# noisemaker_5-0.net
KiCad netlist of a schematic drawn in EAGLE
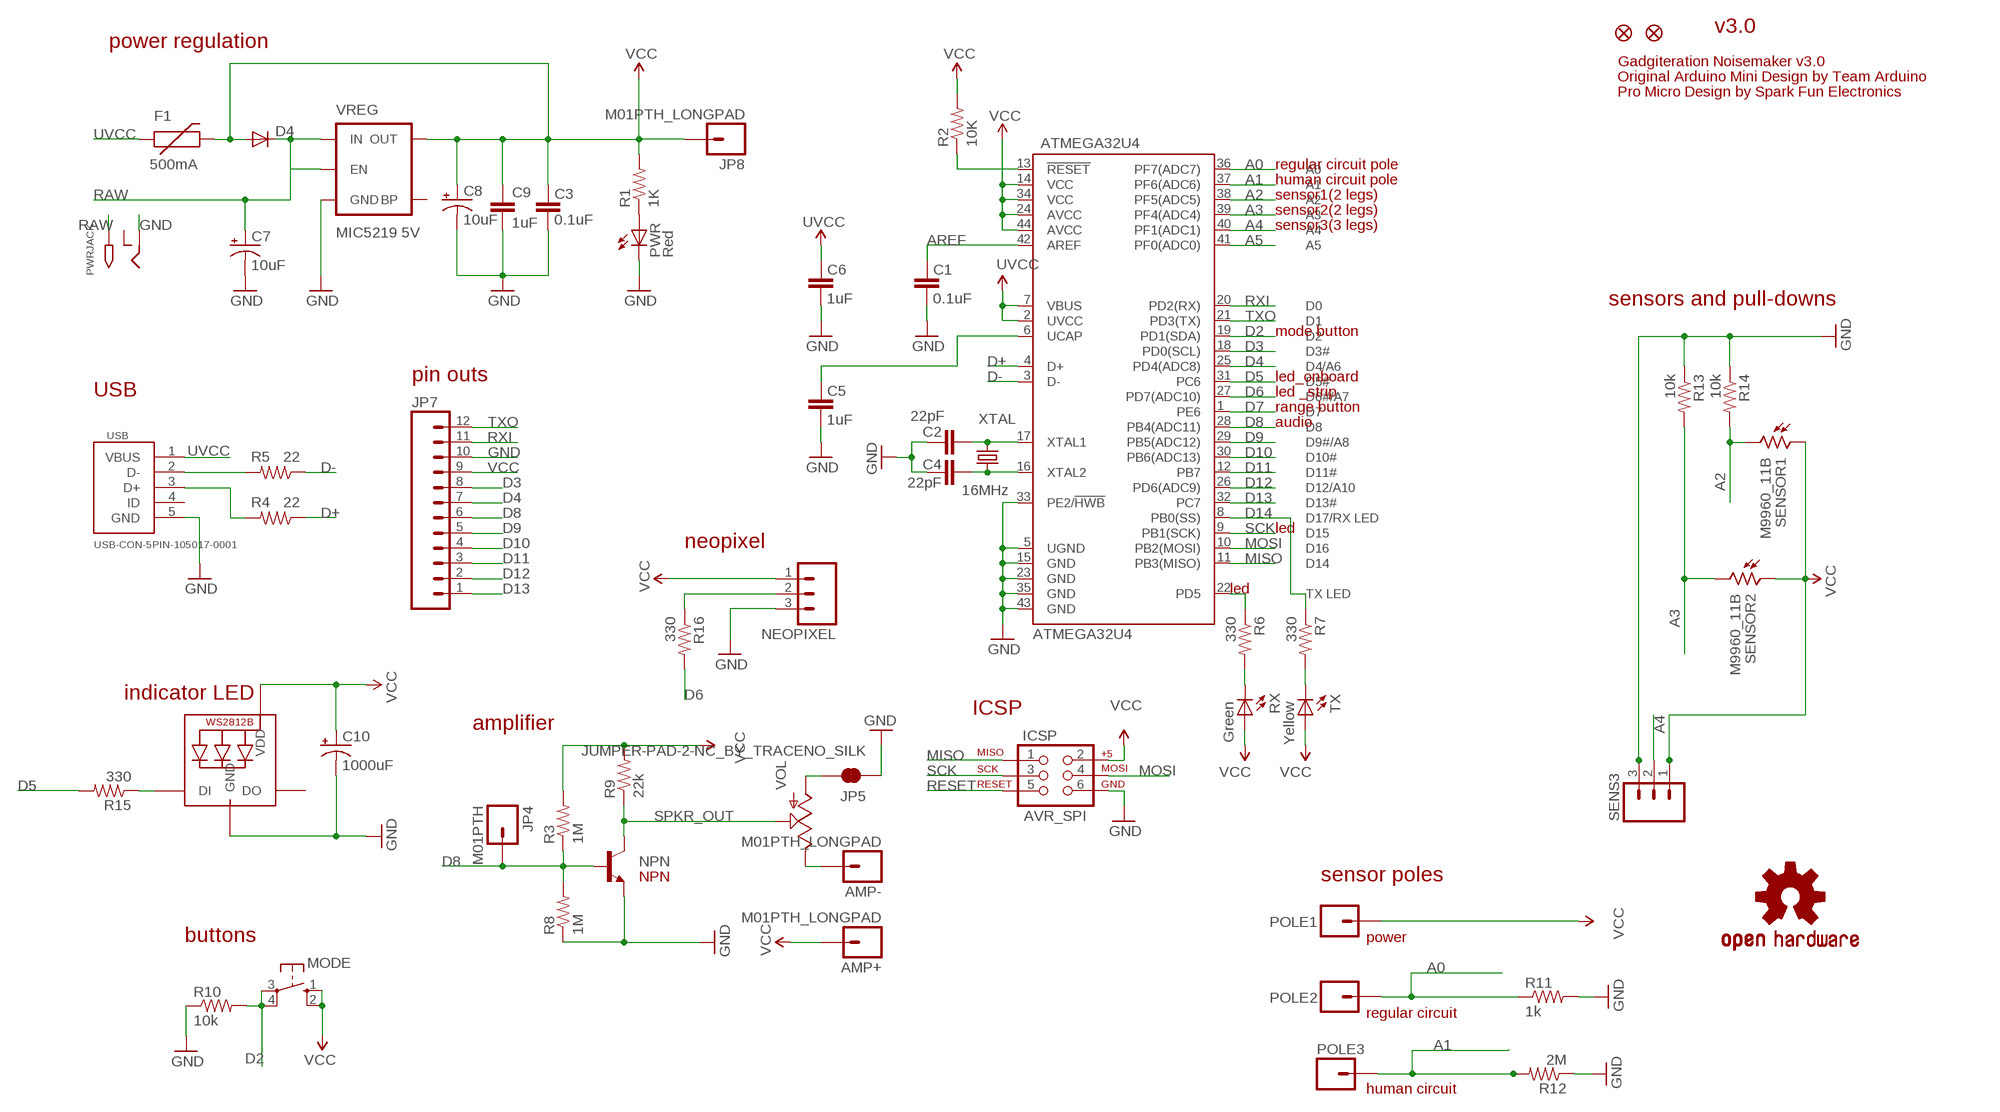
[diagram p0: schematic, sheet 1]

(export (version "E")
  (design (tool "Eeschema 10.0.6"))
  (components
    (comp (ref "AMP+")
      (value "M01PTH_LONGPAD")
      (footprint "eagle-import:1X01_LONGPAD")
      (libsource (lib "eagle-import") (part "M01PTH_LONGPAD"))
    )
    (comp (ref "AMP-")
      (value "M01PTH_LONGPAD")
      (footprint "eagle-import:1X01_LONGPAD")
      (libsource (lib "eagle-import") (part "M01PTH_LONGPAD"))
    )
    (comp (ref "ATMEGA32U4")
      (value "ATMEGA32U4")
      (footprint "eagle-import:SPARKFUN-DIGITALIC_TQFP44")
      (libsource (lib "eagle-import") (part "ATMEGA32U4TQFP"))
    )
    (comp (ref "C1")
      (value "0.1uF")
      (footprint "eagle-import:1206")
      (libsource (lib "eagle-import") (part "SparkFun-Capacitors_CAP1206"))
    )
    (comp (ref "C2")
      (value "22pF")
      (footprint "eagle-import:0603-CAP")
      (libsource (lib "eagle-import") (part "CAP0603-CAP"))
    )
    (comp (ref "C3")
      (value "0.1uF")
      (footprint "eagle-import:1206")
      (libsource (lib "eagle-import") (part "SparkFun-Capacitors_CAP1206"))
    )
    (comp (ref "C4")
      (value "22pF")
      (footprint "eagle-import:0603-CAP")
      (libsource (lib "eagle-import") (part "CAP0603-CAP"))
    )
    (comp (ref "C5")
      (value "1uF")
      (footprint "eagle-import:1206")
      (libsource (lib "eagle-import") (part "SparkFun-Capacitors_CAP1206"))
    )
    (comp (ref "C6")
      (value "1uF")
      (footprint "eagle-import:1206")
      (libsource (lib "eagle-import") (part "SparkFun-Capacitors_CAP1206"))
    )
    (comp (ref "C7")
      (value "10uF")
      (footprint "eagle-import:EIA3528-KIT")
      (libsource (lib "eagle-import") (part "CAP_POL3528-KIT"))
    )
    (comp (ref "C8")
      (value "10uF")
      (footprint "eagle-import:EIA3528-KIT")
      (libsource (lib "eagle-import") (part "CAP_POL3528-KIT"))
    )
    (comp (ref "C9")
      (value "1uF")
      (footprint "eagle-import:1206")
      (libsource (lib "eagle-import") (part "SparkFun-Capacitors_CAP1206"))
    )
    (comp (ref "C10")
      (value "1000uF")
      (footprint "eagle-import:EIA3528-KIT")
      (libsource (lib "eagle-import") (part "CAP_POL3528-KIT"))
    )
    (comp (ref "D4")
      (value "DIODESOD")
      (footprint "eagle-import:SOD-323")
      (libsource (lib "eagle-import") (part "DIODESOD"))
    )
    (comp (ref "F1")
      (value "500mA")
      (footprint "eagle-import:PTC-1206")
      (libsource (lib "eagle-import") (part "PTCSMD"))
    )
    (comp (ref "ICSP")
      (value "AVR_SPI")
      (footprint "eagle-import:2X3")
      (libsource (lib "eagle-import") (part "AVR_SPI_PRG_6PTH"))
    )
    (comp (ref "JP1")
      (value "FIDUCIALUFIDUCIAL")
      (footprint "eagle-import:MICRO-FIDUCIAL")
      (libsource (lib "eagle-import") (part "FIDUCIALUFIDUCIAL"))
    )
    (comp (ref "JP2")
      (value "FIDUCIALUFIDUCIAL")
      (footprint "eagle-import:MICRO-FIDUCIAL")
      (libsource (lib "eagle-import") (part "FIDUCIALUFIDUCIAL"))
    )
    (comp (ref "JP4")
      (value "M01PTH")
      (footprint "eagle-import:1X01")
      (libsource (lib "eagle-import") (part "M01PTH"))
    )
    (comp (ref "JP5")
      (value "JUMPER-PAD-2-NC_BY_TRACENO_SILK")
      (footprint "eagle-import:PAD-JUMPER-2-NC_BY_TRACE_NO_SILK")
      (libsource (lib "eagle-import") (part "JUMPER-PAD-2-NC_BY_TRACENO_SILK"))
    )
    (comp (ref "JP7")
      (value "M12PTH")
      (footprint "eagle-import:1X12")
      (libsource (lib "eagle-import") (part "M12PTH"))
    )
    (comp (ref "JP8")
      (value "M01PTH_LONGPAD")
      (footprint "eagle-import:1X01_LONGPAD")
      (libsource (lib "eagle-import") (part "M01PTH_LONGPAD"))
    )
    (comp (ref "LED1")
      (value "WS2812B3535")
      (footprint "eagle-import:LED3535")
      (libsource (lib "eagle-import") (part "WS2812B3535"))
    )
    (comp (ref "LOGO1")
      (value "OSHW-LOGOM")
      (footprint "eagle-import:OSHW-LOGO-M")
      (libsource (lib "eagle-import") (part "OSHW-LOGOM"))
    )
    (comp (ref "MODE")
      (value "10-XX")
      (footprint "eagle-import:B3F-10XX")
      (libsource (lib "eagle-import") (part "10-XX"))
    )
    (comp (ref "NEOPIXEL")
      (value "M03LONGPADS")
      (footprint "eagle-import:1X03_LONGPADS")
      (libsource (lib "eagle-import") (part "M03LONGPADS"))
    )
    (comp (ref "NPN")
      (value "TRANSISTOR_NPNSOT23-3")
      (footprint "eagle-import:SOT23-3")
      (libsource (lib "eagle-import") (part "TRANSISTOR_NPNSOT23-3"))
    )
    (comp (ref "POLE1")
      (value "M01ALLIGATOR-3MM")
      (footprint "eagle-import:1X01_ALLIGATOR_3MM")
      (libsource (lib "eagle-import") (part "M01ALLIGATOR-3MM"))
    )
    (comp (ref "POLE2")
      (value "M01ALLIGATOR-3MM")
      (footprint "eagle-import:1X01_ALLIGATOR_3MM")
      (libsource (lib "eagle-import") (part "M01ALLIGATOR-3MM"))
    )
    (comp (ref "POLE3")
      (value "M01PTH_LONGPAD")
      (footprint "eagle-import:1X01_LONGPAD")
      (libsource (lib "eagle-import") (part "M01PTH_LONGPAD"))
    )
    (comp (ref "PWR")
      (value "Red")
      (footprint "eagle-import:CHIPLED_1206")
      (libsource (lib "eagle-import") (part "LEDCHIPLED_1206"))
    )
    (comp (ref "PWRJACK")
      (value "2.1MMJACKTHM")
      (footprint "eagle-import:PJ-102A")
      (libsource (lib "eagle-import") (part "2.1MMJACKTHM"))
    )
    (comp (ref "R1")
      (value "1K")
      (footprint "eagle-import:1206")
      (libsource (lib "eagle-import") (part "RESISTOR1206"))
    )
    (comp (ref "R2")
      (value "10K")
      (footprint "eagle-import:1206")
      (libsource (lib "eagle-import") (part "RESISTOR1206"))
    )
    (comp (ref "R3")
      (value "1M")
      (footprint "eagle-import:1206")
      (libsource (lib "eagle-import") (part "RESISTOR1206"))
    )
    (comp (ref "R4")
      (value "22")
      (footprint "eagle-import:1206")
      (libsource (lib "eagle-import") (part "RESISTOR1206"))
    )
    (comp (ref "R5")
      (value "22")
      (footprint "eagle-import:1206")
      (libsource (lib "eagle-import") (part "RESISTOR1206"))
    )
    (comp (ref "R6")
      (value "330")
      (footprint "eagle-import:1206")
      (libsource (lib "eagle-import") (part "RESISTOR1206"))
    )
    (comp (ref "R7")
      (value "330")
      (footprint "eagle-import:1206")
      (libsource (lib "eagle-import") (part "RESISTOR1206"))
    )
    (comp (ref "R8")
      (value "1M")
      (footprint "eagle-import:1206")
      (libsource (lib "eagle-import") (part "RESISTOR1206"))
    )
    (comp (ref "R9")
      (value "22k")
      (footprint "eagle-import:1206")
      (libsource (lib "eagle-import") (part "RESISTOR1206"))
    )
    (comp (ref "R10")
      (value "10k")
      (footprint "eagle-import:1206")
      (libsource (lib "eagle-import") (part "RESISTOR1206"))
    )
    (comp (ref "R11")
      (value "1k")
      (footprint "eagle-import:1206")
      (libsource (lib "eagle-import") (part "RESISTOR1206"))
    )
    (comp (ref "R12")
      (value "2M")
      (footprint "eagle-import:1206")
      (libsource (lib "eagle-import") (part "RESISTOR1206"))
    )
    (comp (ref "R13")
      (value "10k")
      (footprint "eagle-import:1206")
      (libsource (lib "eagle-import") (part "RESISTOR1206"))
    )
    (comp (ref "R14")
      (value "10k")
      (footprint "eagle-import:1206")
      (libsource (lib "eagle-import") (part "RESISTOR1206"))
    )
    (comp (ref "R15")
      (value "330")
      (footprint "eagle-import:1206")
      (libsource (lib "eagle-import") (part "RESISTOR1206"))
    )
    (comp (ref "R16")
      (value "330")
      (footprint "eagle-import:1206")
      (libsource (lib "eagle-import") (part "RESISTOR1206"))
    )
    (comp (ref "RX")
      (value "Green")
      (footprint "eagle-import:CHIPLED_1206")
      (libsource (lib "eagle-import") (part "LEDCHIPLED_1206"))
    )
    (comp (ref "SENS3")
      (value "M03POGO_PIN_HOLES_ONLY")
      (footprint "eagle-import:1X03_PP_HOLES_ONLY")
      (libsource (lib "eagle-import") (part "M03POGO_PIN_HOLES_ONLY"))
    )
    (comp (ref "SENSOR1")
      (value "M9960_11B")
      (footprint "eagle-import:M9960")
      (libsource (lib "eagle-import") (part "M9960_11B"))
    )
    (comp (ref "SENSOR2")
      (value "M9960_11B")
      (footprint "eagle-import:M9960")
      (libsource (lib "eagle-import") (part "M9960_11B"))
    )
    (comp (ref "TX")
      (value "Yellow")
      (footprint "eagle-import:CHIPLED_1206")
      (libsource (lib "eagle-import") (part "LEDCHIPLED_1206"))
    )
    (comp (ref "USB")
      (value "USB-CON-5PIN-105017-0001")
      (footprint "eagle-import:USB-MICRO-MOLEX-105017-0001")
      (libsource (lib "eagle-import") (part "USB-CON-5PIN-105017-0001"))
    )
    (comp (ref "VOL")
      (value "POT")
      (footprint "eagle-import:ALPS_POT")
      (libsource (lib "eagle-import") (part "POT"))
    )
    (comp (ref "VREG")
      (value "MIC5219 5V")
      (footprint "eagle-import:SOT23-5")
      (libsource (lib "eagle-import") (part "V_REG_MIC52195V"))
    )
    (comp (ref "XTAL")
      (value "16MHz")
      (footprint "eagle-import:CRYSTAL-SMD-5X3")
      (libsource (lib "eagle-import") (part "CRYSTAL5X3"))
    )
  )
  (nets
    (net (code "1") (name "/A0") (class "Default")
      (node (ref "ATMEGA32U4") (pin "36") (pinfunction "PF7(ADC7)_36") (pintype "bidirectional"))
      (node (ref "POLE2") (pin "1@0") (pinfunction "1_1@0") (pintype "passive"))
      (node (ref "POLE2") (pin "1@2") (pinfunction "1_1@2") (pintype "passive"))
      (node (ref "R11") (pin "1") (pinfunction "1_1") (pintype "passive"))
    )
    (net (code "2") (name "/A1") (class "Default")
      (node (ref "ATMEGA32U4") (pin "37") (pinfunction "PF6(ADC6)_37") (pintype "bidirectional"))
      (node (ref "POLE3") (pin "1") (pinfunction "1_1") (pintype "passive"))
      (node (ref "R12") (pin "2") (pinfunction "2_2") (pintype "passive"))
    )
    (net (code "3") (name "/A2") (class "Default")
      (node (ref "ATMEGA32U4") (pin "38") (pinfunction "PF5(ADC5)_38") (pintype "bidirectional"))
      (node (ref "R14") (pin "2") (pinfunction "2_2") (pintype "passive"))
      (node (ref "SENSOR1") (pin "2") (pinfunction "2_2") (pintype "passive"))
    )
    (net (code "4") (name "/A3") (class "Default")
      (node (ref "ATMEGA32U4") (pin "39") (pinfunction "PF4(ADC4)_39") (pintype "bidirectional"))
      (node (ref "R13") (pin "2") (pinfunction "2_2") (pintype "passive"))
      (node (ref "SENSOR2") (pin "2") (pinfunction "2_2") (pintype "passive"))
    )
    (net (code "5") (name "/A4") (class "Default")
      (node (ref "ATMEGA32U4") (pin "40") (pinfunction "PF1(ADC1)_40") (pintype "bidirectional"))
      (node (ref "SENS3") (pin "2") (pinfunction "2_2") (pintype "passive"))
    )
    (net (code "6") (name "/A5") (class "Default")
      (node (ref "ATMEGA32U4") (pin "41") (pinfunction "PF0(ADC0)_41") (pintype "bidirectional"))
    )
    (net (code "7") (name "/AREF") (class "Default")
      (node (ref "ATMEGA32U4") (pin "42") (pinfunction "AREF_42") (pintype "bidirectional"))
      (node (ref "C1") (pin "2") (pinfunction "2_2") (pintype "passive"))
    )
    (net (code "8") (name "/D+") (class "Default")
      (node (ref "ATMEGA32U4") (pin "4") (pinfunction "D+_4") (pintype "bidirectional"))
      (node (ref "R4") (pin "1") (pinfunction "1_1") (pintype "passive"))
    )
    (net (code "9") (name "/D-") (class "Default")
      (node (ref "ATMEGA32U4") (pin "3") (pinfunction "D-_3") (pintype "bidirectional"))
      (node (ref "R5") (pin "1") (pinfunction "1_1") (pintype "passive"))
    )
    (net (code "10") (name "/D2") (class "Default")
      (node (ref "ATMEGA32U4") (pin "19") (pinfunction "PD1(SDA)_19") (pintype "bidirectional"))
      (node (ref "MODE") (pin "3") (pinfunction "P_3") (pintype "passive"))
      (node (ref "MODE") (pin "4") (pinfunction "P1_4") (pintype "passive"))
      (node (ref "R10") (pin "2") (pinfunction "2_2") (pintype "passive"))
    )
    (net (code "11") (name "/D3") (class "Default")
      (node (ref "ATMEGA32U4") (pin "18") (pinfunction "PD0(SCL)_18") (pintype "bidirectional"))
      (node (ref "JP7") (pin "8") (pinfunction "8_8") (pintype "passive"))
    )
    (net (code "12") (name "/D4") (class "Default")
      (node (ref "ATMEGA32U4") (pin "25") (pinfunction "PD4(ADC8)_25") (pintype "bidirectional"))
      (node (ref "JP7") (pin "7") (pinfunction "7_7") (pintype "passive"))
    )
    (net (code "13") (name "/D5") (class "Default")
      (node (ref "ATMEGA32U4") (pin "31") (pinfunction "PC6_31") (pintype "bidirectional"))
      (node (ref "R15") (pin "2") (pinfunction "2_2") (pintype "passive"))
    )
    (net (code "14") (name "/D6") (class "Default")
      (node (ref "ATMEGA32U4") (pin "27") (pinfunction "PD7(ADC10)_27") (pintype "bidirectional"))
      (node (ref "R16") (pin "2") (pinfunction "2_2") (pintype "passive"))
    )
    (net (code "15") (name "/D7") (class "Default")
      (node (ref "ATMEGA32U4") (pin "1") (pinfunction "PE6_1") (pintype "bidirectional"))
    )
    (net (code "16") (name "/D8") (class "Default")
      (node (ref "ATMEGA32U4") (pin "28") (pinfunction "PB4(ADC11)_28") (pintype "bidirectional"))
      (node (ref "JP4") (pin "1") (pinfunction "1_1") (pintype "passive"))
      (node (ref "JP7") (pin "6") (pinfunction "6_6") (pintype "passive"))
      (node (ref "NPN") (pin "1") (pinfunction "B_1") (pintype "passive"))
      (node (ref "R3") (pin "1") (pinfunction "1_1") (pintype "passive"))
      (node (ref "R8") (pin "2") (pinfunction "2_2") (pintype "passive"))
    )
    (net (code "17") (name "/D9") (class "Default")
      (node (ref "ATMEGA32U4") (pin "29") (pinfunction "PB5(ADC12)_29") (pintype "bidirectional"))
      (node (ref "JP7") (pin "5") (pinfunction "5_5") (pintype "passive"))
    )
    (net (code "18") (name "/D10") (class "Default")
      (node (ref "ATMEGA32U4") (pin "30") (pinfunction "PB6(ADC13)_30") (pintype "bidirectional"))
      (node (ref "JP7") (pin "4") (pinfunction "4_4") (pintype "passive"))
    )
    (net (code "19") (name "/D11") (class "Default")
      (node (ref "ATMEGA32U4") (pin "12") (pinfunction "PB7_12") (pintype "bidirectional"))
      (node (ref "JP7") (pin "3") (pinfunction "3_3") (pintype "passive"))
    )
    (net (code "20") (name "/D12") (class "Default")
      (node (ref "ATMEGA32U4") (pin "26") (pinfunction "PD6(ADC9)_26") (pintype "bidirectional"))
      (node (ref "JP7") (pin "2") (pinfunction "2_2") (pintype "passive"))
    )
    (net (code "21") (name "/D13") (class "Default")
      (node (ref "ATMEGA32U4") (pin "32") (pinfunction "PC7_32") (pintype "bidirectional"))
      (node (ref "JP7") (pin "1") (pinfunction "1_1") (pintype "passive"))
    )
    (net (code "22") (name "/D14") (class "Default")
      (node (ref "ATMEGA32U4") (pin "8") (pinfunction "PB0(SS)_8") (pintype "bidirectional"))
      (node (ref "R7") (pin "1") (pinfunction "1_1") (pintype "passive"))
    )
    (net (code "23") (name "/MISO") (class "Default")
      (node (ref "ATMEGA32U4") (pin "11") (pinfunction "PB3(MISO)_11") (pintype "bidirectional"))
      (node (ref "ICSP") (pin "1") (pinfunction "1_1") (pintype "passive"))
    )
    (net (code "24") (name "/MOSI") (class "Default")
      (node (ref "ATMEGA32U4") (pin "10") (pinfunction "PB2(MOSI)_10") (pintype "bidirectional"))
      (node (ref "ICSP") (pin "4") (pinfunction "4_4") (pintype "passive"))
    )
    (net (code "25") (name "/RAW") (class "Default")
      (node (ref "C7") (pin "A") (pinfunction "+_A") (pintype "passive"))
      (node (ref "D4") (pin "1") (pinfunction "C_1") (pintype "passive"))
      (node (ref "PWRJACK") (pin "TIP") (pinfunction "TIP_TIP") (pintype "bidirectional"))
      (node (ref "VREG") (pin "1") (pinfunction "IN_1") (pintype "input"))
      (node (ref "VREG") (pin "3") (pinfunction "EN_3") (pintype "input"))
    )
    (net (code "26") (name "/RESET") (class "Default")
      (node (ref "ATMEGA32U4") (pin "13") (pinfunction "~{RESET}_13") (pintype "bidirectional"))
      (node (ref "ICSP") (pin "5") (pinfunction "5_5") (pintype "passive"))
      (node (ref "R2") (pin "1") (pinfunction "1_1") (pintype "passive"))
    )
    (net (code "27") (name "/RXI") (class "Default")
      (node (ref "ATMEGA32U4") (pin "20") (pinfunction "PD2(RX)_20") (pintype "bidirectional"))
      (node (ref "JP7") (pin "11") (pinfunction "11_11") (pintype "passive"))
    )
    (net (code "28") (name "/SCK") (class "Default")
      (node (ref "ATMEGA32U4") (pin "9") (pinfunction "PB1(SCK)_9") (pintype "bidirectional"))
      (node (ref "ICSP") (pin "3") (pinfunction "3_3") (pintype "passive"))
    )
    (net (code "29") (name "/SPKR_OUT") (class "Default")
      (node (ref "NPN") (pin "3") (pinfunction "C_3") (pintype "passive"))
      (node (ref "R9") (pin "1") (pinfunction "1_1") (pintype "passive"))
      (node (ref "VOL") (pin "P$2") (pinfunction "S_P$2") (pintype "passive"))
    )
    (net (code "30") (name "/TXO") (class "Default")
      (node (ref "ATMEGA32U4") (pin "21") (pinfunction "PD3(TX)_21") (pintype "bidirectional"))
      (node (ref "JP7") (pin "12") (pinfunction "12_12") (pintype "passive"))
    )
    (net (code "31") (name "GND") (class "Default")
      (node (ref "ATMEGA32U4") (pin "15") (pinfunction "GND_15") (pintype "bidirectional"))
      (node (ref "ATMEGA32U4") (pin "23") (pinfunction "GND_23") (pintype "bidirectional"))
      (node (ref "ATMEGA32U4") (pin "33") (pinfunction "PE2/~{HWB}_33") (pintype "bidirectional"))
      (node (ref "ATMEGA32U4") (pin "35") (pinfunction "GND_35") (pintype "bidirectional"))
      (node (ref "ATMEGA32U4") (pin "43") (pinfunction "GND_43") (pintype "bidirectional"))
      (node (ref "ATMEGA32U4") (pin "5") (pinfunction "UGND_5") (pintype "bidirectional"))
      (node (ref "C1") (pin "1") (pinfunction "1_1") (pintype "passive"))
      (node (ref "C10") (pin "C") (pinfunction "-_C") (pintype "passive"))
      (node (ref "C2") (pin "2") (pinfunction "2_2") (pintype "passive"))
      (node (ref "C3") (pin "1") (pinfunction "1_1") (pintype "passive"))
      (node (ref "C4") (pin "2") (pinfunction "2_2") (pintype "passive"))
      (node (ref "C5") (pin "1") (pinfunction "1_1") (pintype "passive"))
      (node (ref "C6") (pin "1") (pinfunction "1_1") (pintype "passive"))
      (node (ref "C7") (pin "C") (pinfunction "-_C") (pintype "passive"))
      (node (ref "C8") (pin "C") (pinfunction "-_C") (pintype "passive"))
      (node (ref "C9") (pin "2") (pinfunction "2_2") (pintype "passive"))
      (node (ref "ICSP") (pin "6") (pinfunction "6_6") (pintype "passive"))
      (node (ref "JP5") (pin "1") (pinfunction "1_1") (pintype "passive"))
      (node (ref "JP7") (pin "10") (pinfunction "10_10") (pintype "passive"))
      (node (ref "LED1") (pin "4") (pinfunction "GND_4") (pintype "power_in"))
      (node (ref "NEOPIXEL") (pin "3") (pinfunction "3_3") (pintype "passive"))
      (node (ref "NPN") (pin "2") (pinfunction "E_2") (pintype "passive"))
      (node (ref "PWR") (pin "C") (pinfunction "C_C") (pintype "passive"))
      (node (ref "PWRJACK") (pin "RING") (pinfunction "RING_RING") (pintype "bidirectional"))
      (node (ref "R10") (pin "1") (pinfunction "1_1") (pintype "passive"))
      (node (ref "R11") (pin "2") (pinfunction "2_2") (pintype "passive"))
      (node (ref "R12") (pin "1") (pinfunction "1_1") (pintype "passive"))
      (node (ref "R13") (pin "1") (pinfunction "1_1") (pintype "passive"))
      (node (ref "R14") (pin "1") (pinfunction "1_1") (pintype "passive"))
      (node (ref "R8") (pin "1") (pinfunction "1_1") (pintype "passive"))
      (node (ref "SENS3") (pin "3") (pinfunction "3_3") (pintype "passive"))
      (node (ref "USB") (pin "5") (pinfunction "GND_5") (pintype "power_in"))
      (node (ref "VREG") (pin "2") (pinfunction "GND_2") (pintype "input"))
    )
    (net (code "32") (name "Net-(ATMEGA32U4-PD5)") (class "Default")
      (node (ref "ATMEGA32U4") (pin "22") (pinfunction "PD5_22") (pintype "bidirectional"))
      (node (ref "R6") (pin "1") (pinfunction "1_1") (pintype "passive"))
    )
    (net (code "33") (name "Net-(ATMEGA32U4-UCAP)") (class "Default")
      (node (ref "ATMEGA32U4") (pin "6") (pinfunction "UCAP_6") (pintype "bidirectional"))
      (node (ref "C5") (pin "2") (pinfunction "2_2") (pintype "passive"))
    )
    (net (code "34") (name "Net-(ATMEGA32U4-XTAL1)") (class "Default")
      (node (ref "ATMEGA32U4") (pin "17") (pinfunction "XTAL1_17") (pintype "bidirectional"))
      (node (ref "C2") (pin "1") (pinfunction "1_1") (pintype "passive"))
      (node (ref "XTAL") (pin "3") (pinfunction "2_3") (pintype "passive"))
    )
    (net (code "35") (name "Net-(ATMEGA32U4-XTAL2)") (class "Default")
      (node (ref "ATMEGA32U4") (pin "16") (pinfunction "XTAL2_16") (pintype "bidirectional"))
      (node (ref "C4") (pin "1") (pinfunction "1_1") (pintype "passive"))
      (node (ref "XTAL") (pin "1") (pinfunction "1_1") (pintype "passive"))
    )
    (net (code "36") (name "Net-(LED1-DI)") (class "Default")
      (node (ref "LED1") (pin "1") (pinfunction "DI_1") (pintype "input"))
      (node (ref "R15") (pin "1") (pinfunction "1_1") (pintype "passive"))
    )
    (net (code "37") (name "Net-(NEOPIXEL-Pad2)") (class "Default")
      (node (ref "NEOPIXEL") (pin "2") (pinfunction "2_2") (pintype "passive"))
      (node (ref "R16") (pin "1") (pinfunction "1_1") (pintype "passive"))
    )
    (net (code "38") (name "Net-(PWR-PadA)") (class "Default")
      (node (ref "PWR") (pin "A") (pinfunction "A_A") (pintype "passive"))
      (node (ref "R1") (pin "1") (pinfunction "1_1") (pintype "passive"))
    )
    (net (code "39") (name "Net-(R6-Pad2)") (class "Default")
      (node (ref "R6") (pin "2") (pinfunction "2_2") (pintype "passive"))
      (node (ref "RX") (pin "C") (pinfunction "C_C") (pintype "passive"))
    )
    (net (code "40") (name "Net-(R7-Pad2)") (class "Default")
      (node (ref "R7") (pin "2") (pinfunction "2_2") (pintype "passive"))
      (node (ref "TX") (pin "C") (pinfunction "C_C") (pintype "passive"))
    )
    (net (code "41") (name "Net-(USB-D+)") (class "Default")
      (node (ref "R4") (pin "2") (pinfunction "2_2") (pintype "passive"))
      (node (ref "USB") (pin "3") (pinfunction "D+_3") (pintype "bidirectional"))
    )
    (net (code "42") (name "Net-(USB-D-)") (class "Default")
      (node (ref "R5") (pin "2") (pinfunction "2_2") (pintype "passive"))
      (node (ref "USB") (pin "2") (pinfunction "D-_2") (pintype "bidirectional"))
    )
    (net (code "43") (name "Net-(VOL-A)") (class "Default")
      (node (ref "JP5") (pin "2") (pinfunction "2_2") (pintype "passive"))
      (node (ref "VOL") (pin "P$3") (pinfunction "A_P$3") (pintype "passive"))
    )
    (net (code "44") (name "Net-(VOL-E)") (class "Default")
      (node (ref "AMP-") (pin "1") (pinfunction "1_1") (pintype "passive"))
      (node (ref "VOL") (pin "P$1") (pinfunction "E_P$1") (pintype "passive"))
    )
    (net (code "45") (name "UVCC") (class "Default")
      (node (ref "ATMEGA32U4") (pin "2") (pinfunction "UVCC_2") (pintype "bidirectional"))
      (node (ref "ATMEGA32U4") (pin "7") (pinfunction "VBUS_7") (pintype "bidirectional"))
      (node (ref "C6") (pin "2") (pinfunction "2_2") (pintype "passive"))
      (node (ref "F1") (pin "1") (pinfunction "1_1") (pintype "bidirectional"))
      (node (ref "USB") (pin "1") (pinfunction "VBUS_1") (pintype "power_in"))
    )
    (net (code "46") (name "VCC") (class "Default")
      (node (ref "AMP+") (pin "1") (pinfunction "1_1") (pintype "passive"))
      (node (ref "ATMEGA32U4") (pin "14") (pinfunction "VCC_14") (pintype "bidirectional"))
      (node (ref "ATMEGA32U4") (pin "24") (pinfunction "AVCC_24") (pintype "bidirectional"))
      (node (ref "ATMEGA32U4") (pin "34") (pinfunction "VCC_34") (pintype "bidirectional"))
      (node (ref "ATMEGA32U4") (pin "44") (pinfunction "AVCC_44") (pintype "bidirectional"))
      (node (ref "C10") (pin "A") (pinfunction "+_A") (pintype "passive"))
      (node (ref "C3") (pin "2") (pinfunction "2_2") (pintype "passive"))
      (node (ref "C8") (pin "A") (pinfunction "+_A") (pintype "passive"))
      (node (ref "C9") (pin "1") (pinfunction "1_1") (pintype "passive"))
      (node (ref "D4") (pin "2") (pinfunction "A_2") (pintype "passive"))
      (node (ref "F1") (pin "2") (pinfunction "2_2") (pintype "bidirectional"))
      (node (ref "ICSP") (pin "2") (pinfunction "2_2") (pintype "passive"))
      (node (ref "JP7") (pin "9") (pinfunction "9_9") (pintype "passive"))
      (node (ref "JP8") (pin "1") (pinfunction "1_1") (pintype "passive"))
      (node (ref "LED1") (pin "2") (pinfunction "VDD_2") (pintype "power_in"))
      (node (ref "MODE") (pin "1") (pinfunction "S_1") (pintype "passive"))
      (node (ref "MODE") (pin "2") (pinfunction "S1_2") (pintype "passive"))
      (node (ref "NEOPIXEL") (pin "1") (pinfunction "1_1") (pintype "passive"))
      (node (ref "POLE1") (pin "1@0") (pinfunction "1_1@0") (pintype "passive"))
      (node (ref "POLE1") (pin "1@2") (pinfunction "1_1@2") (pintype "passive"))
      (node (ref "R1") (pin "2") (pinfunction "2_2") (pintype "passive"))
      (node (ref "R2") (pin "2") (pinfunction "2_2") (pintype "passive"))
      (node (ref "R3") (pin "2") (pinfunction "2_2") (pintype "passive"))
      (node (ref "R9") (pin "2") (pinfunction "2_2") (pintype "passive"))
      (node (ref "RX") (pin "A") (pinfunction "A_A") (pintype "passive"))
      (node (ref "SENS3") (pin "1") (pinfunction "1_1") (pintype "passive"))
      (node (ref "SENSOR1") (pin "1") (pinfunction "1_1") (pintype "passive"))
      (node (ref "SENSOR2") (pin "1") (pinfunction "1_1") (pintype "passive"))
      (node (ref "TX") (pin "A") (pinfunction "A_A") (pintype "passive"))
      (node (ref "VREG") (pin "5") (pinfunction "OUT_5") (pintype "passive"))
    )
    (net (code "47") (name "unconnected-(LED1-DO-Pad3)") (class "Default")
      (node (ref "LED1") (pin "3") (pinfunction "DO_3") (pintype "output"))
    )
    (net (code "48") (name "unconnected-(PWRJACK-PadRING_SW)") (class "Default")
      (node (ref "PWRJACK") (pin "RING_SW") (pinfunction "RING_SW_RING_SW") (pintype "bidirectional"))
    )
    (net (code "49") (name "unconnected-(USB-ID-Pad4)") (class "Default")
      (node (ref "USB") (pin "4") (pinfunction "ID_4") (pintype "bidirectional"))
    )
    (net (code "50") (name "unconnected-(VREG-BP-Pad4)") (class "Default")
      (node (ref "VREG") (pin "4") (pinfunction "BP_4") (pintype "input"))
    )
  )
)
